# LPCB279_-_POWER.net
KiCad netlist of a schematic drawn in Altium Designer
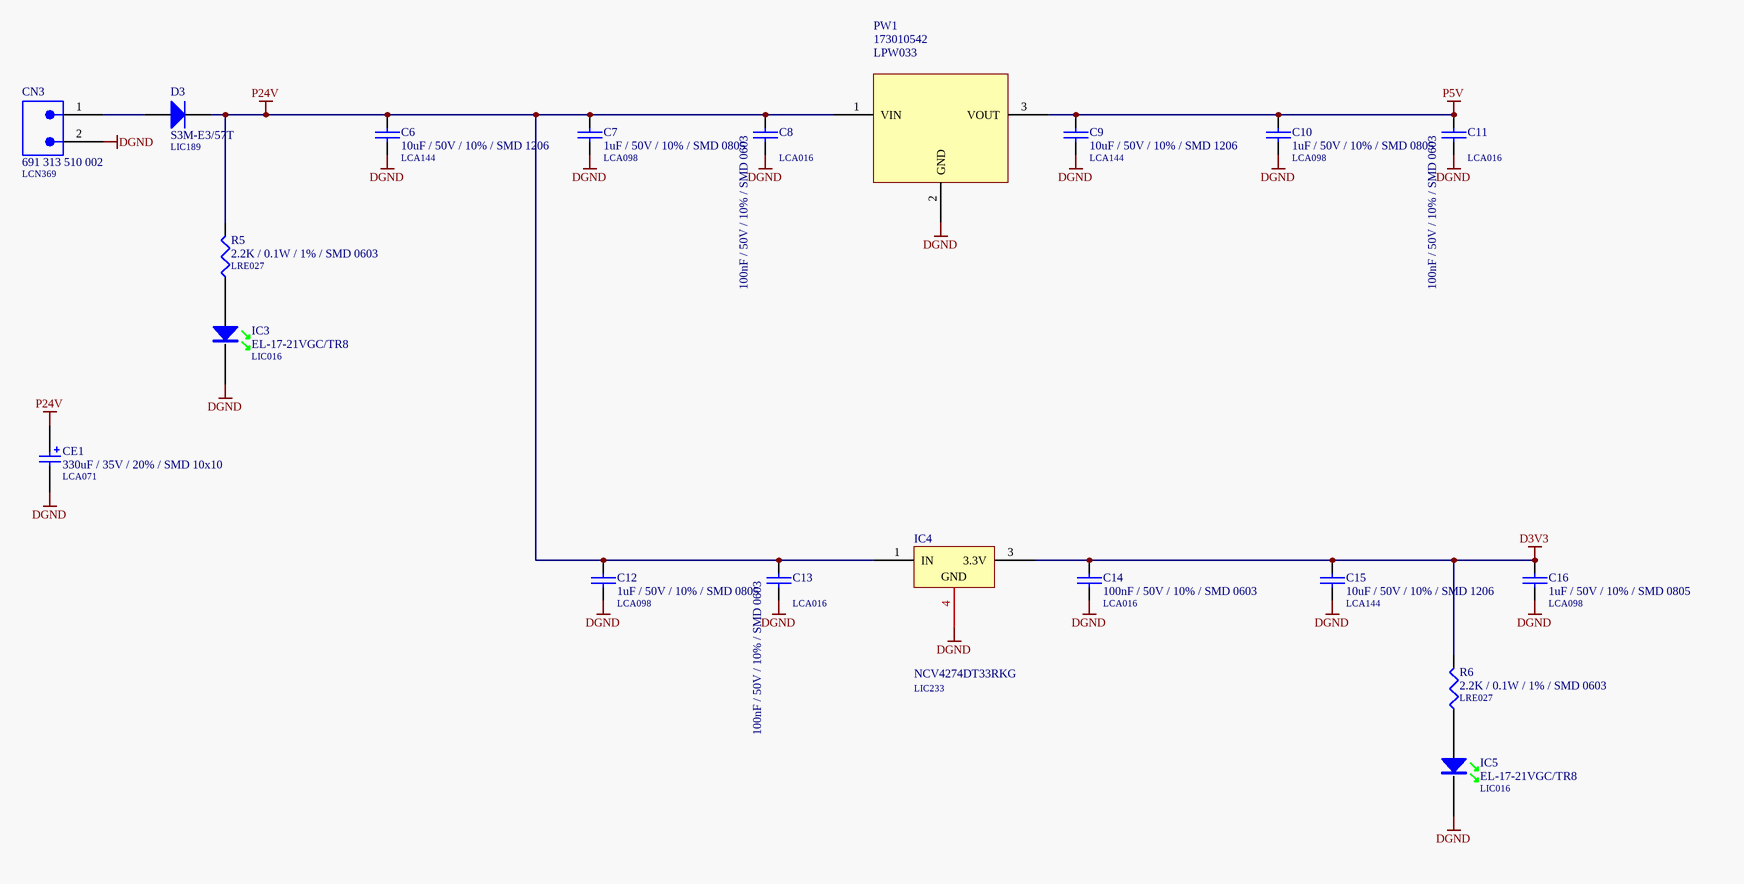
[diagram p0: LPCB279 - POWER.SchDoc]

(export (version "E")
  (design (tool "Eeschema 10.0.6"))
  (components
    (comp (ref "C6")
      (value "10uF / 50V / 10% / SMD 1206")
      (footprint "LFP043__CC3216-1206")
      (description "Capacitor, Ceramic Chip, 10uF, 50V, X5R, 10%, SMD 1206 [LCA144]")
      (fields (field (name "LDL_NUMBER") "LCA144"))
      (libsource (lib "LDL_Capacitors") (part "10uF / 50V / 10% / SMD 1206"))
    )
    (comp (ref "C7")
      (value "1uF / 50V / 10% / SMD 0805")
      (footprint "LFP010__CC2012-0805-IPC7351_B")
      (description "Capacitor, Ceramic Chip, 1uF, 50V, SMD 0805 [LCA098]")
      (fields (field (name "LDL_NUMBER") "LCA098"))
      (libsource (lib "LDL_Capacitors") (part "1uF / 50V / 10% / SMD 0805"))
    )
    (comp (ref "C8")
      (value "100nF / 50V / 10% / SMD 0603")
      (footprint "LFP011__CC1608-0603-IPC7351_B")
      (description "Capacitor, Ceramic Chip, 100nF (0.1uF), 50V, 5%, SMD 0603 [LCA016]")
      (fields (field (name "LDL_NUMBER") "LCA016"))
      (libsource (lib "LDL_Capacitors") (part "100nF / 50V / 10% / SMD 0603"))
    )
    (comp (ref "C9")
      (value "10uF / 50V / 10% / SMD 1206")
      (footprint "LFP043__CC3216-1206")
      (description "Capacitor, Ceramic Chip, 10uF, 50V, X5R, 10%, SMD 1206 [LCA144]")
      (fields (field (name "LDL_NUMBER") "LCA144"))
      (libsource (lib "LDL_Capacitors") (part "10uF / 50V / 10% / SMD 1206"))
    )
    (comp (ref "C10")
      (value "1uF / 50V / 10% / SMD 0805")
      (footprint "LFP010__CC2012-0805-IPC7351_B")
      (description "Capacitor, Ceramic Chip, 1uF, 50V, SMD 0805 [LCA098]")
      (fields (field (name "LDL_NUMBER") "LCA098"))
      (libsource (lib "LDL_Capacitors") (part "1uF / 50V / 10% / SMD 0805"))
    )
    (comp (ref "C11")
      (value "100nF / 50V / 10% / SMD 0603")
      (footprint "LFP011__CC1608-0603-IPC7351_B")
      (description "Capacitor, Ceramic Chip, 100nF (0.1uF), 50V, 5%, SMD 0603 [LCA016]")
      (fields (field (name "LDL_NUMBER") "LCA016"))
      (libsource (lib "LDL_Capacitors") (part "100nF / 50V / 10% / SMD 0603"))
    )
    (comp (ref "C12")
      (value "1uF / 50V / 10% / SMD 0805")
      (footprint "LFP010__CC2012-0805-IPC7351_B")
      (description "Capacitor, Ceramic Chip, 1uF, 50V, SMD 0805 [LCA098]")
      (fields (field (name "LDL_NUMBER") "LCA098"))
      (libsource (lib "LDL_Capacitors") (part "1uF / 50V / 10% / SMD 0805"))
    )
    (comp (ref "C13")
      (value "100nF / 50V / 10% / SMD 0603")
      (footprint "LFP011__CC1608-0603-IPC7351_B")
      (description "Capacitor, Ceramic Chip, 100nF (0.1uF), 50V, 5%, SMD 0603 [LCA016]")
      (fields (field (name "LDL_NUMBER") "LCA016"))
      (libsource (lib "LDL_Capacitors") (part "100nF / 50V / 10% / SMD 0603"))
    )
    (comp (ref "C14")
      (value "100nF / 50V / 10% / SMD 0603")
      (footprint "LFP011__CC1608-0603-IPC7351_B")
      (description "Capacitor, Ceramic Chip, 100nF (0.1uF), 50V, 5%, SMD 0603 [LCA016]")
      (fields (field (name "LDL_NUMBER") "LCA016"))
      (libsource (lib "LDL_Capacitors") (part "100nF / 50V / 10% / SMD 0603"))
    )
    (comp (ref "C15")
      (value "10uF / 50V / 10% / SMD 1206")
      (footprint "LFP043__CC3216-1206")
      (description "Capacitor, Ceramic Chip, 10uF, 50V, X5R, 10%, SMD 1206 [LCA144]")
      (fields (field (name "LDL_NUMBER") "LCA144"))
      (libsource (lib "LDL_Capacitors") (part "10uF / 50V / 10% / SMD 1206"))
    )
    (comp (ref "C16")
      (value "1uF / 50V / 10% / SMD 0805")
      (footprint "LFP010__CC2012-0805-IPC7351_B")
      (description "Capacitor, Ceramic Chip, 1uF, 50V, SMD 0805 [LCA098]")
      (fields (field (name "LDL_NUMBER") "LCA098"))
      (libsource (lib "LDL_Capacitors") (part "1uF / 50V / 10% / SMD 0805"))
    )
    (comp (ref "CE1")
      (value "330uF / 35V / 20% / SMD 10x10")
      (footprint "LFP041__NICHICON_WT_10X10")
      (description "Capacitor, Aluminum Electrolytic, 330uF, 35V, 20%, SMD (10mm x 10mm) [LCA071]")
      (fields (field (name "LDL_NUMBER") "LCA071"))
      (libsource (lib "LDL_Capacitors") (part "330uF / 35V / 20% / SMD 10x10"))
    )
    (comp (ref "CN3")
      (value "691 313 510 002")
      (footprint "691 313 510 002")
      (description "Connector, Pluggable Terminal Block, 5.08mm, 2 Way, PTH")
      (fields (field (name "LDL_NUMBER") "LCN369"))
      (libsource (lib "LDL_Connectors") (part "691 313 510 002"))
    )
    (comp (ref "D3")
      (value "S3M-E3/57T")
      (footprint "LFP040__DO-214AB")
      (description "Diode, General Purpose Rectifier, 3A, 200V, SMD DO-214AB [LIC189]")
      (fields (field (name "LDL_NUMBER") "LIC189"))
      (libsource (lib "LDL_Semiconductors") (part "S3M-E3/57T"))
    )
    (comp (ref "IC3")
      (value "EL-17-21VGC/TR8")
      (footprint "CR2012-0805-LED")
      (description "LED, SMD, 0805 Green [LIC016]")
      (fields (field (name "LDL_NUMBER") "LIC016"))
      (libsource (lib "LDL_Semiconductors") (part "EL-17-21VGC/TR8"))
    )
    (comp (ref "IC4")
      (value "NCV4274DT33RKG")
      (footprint "LFP019__369A-13")
      (description "IC, Voltage Regulator, 400mA, 3.3V LDO, SMD DPAK [LIC233]")
      (fields (field (name "LDL_NUMBER") "LIC233"))
      (libsource (lib "LDL_Semiconductors") (part "NCV4274DT33RKG"))
    )
    (comp (ref "IC5")
      (value "EL-17-21VGC/TR8")
      (footprint "CR2012-0805-LED")
      (description "LED, SMD, 0805 Green [LIC016]")
      (fields (field (name "LDL_NUMBER") "LIC016"))
      (libsource (lib "LDL_Semiconductors") (part "EL-17-21VGC/TR8"))
    )
    (comp (ref "PW1")
      (value "173010542")
      (footprint "173010542")
      (fields (field (name "LDL_NUMBER") "LPW033"))
      (libsource (lib "LDL_Power") (part "173010542"))
    )
    (comp (ref "R5")
      (value "2.2K / 0.1W / 1% / SMD 0603")
      (footprint "LFP020__CR1608-0603-IPC7351_B")
      (description "Resistor, Ceramic Chip, 2.2K, 0.1W, 1%, SMD 0603 [LRE027]")
      (fields (field (name "LDL_NUMBER") "LRE027"))
      (libsource (lib "LDL_Resistors") (part "2.2K / 0.1W / 1% / SMD 0603"))
    )
    (comp (ref "R6")
      (value "2.2K / 0.1W / 1% / SMD 0603")
      (footprint "LFP020__CR1608-0603-IPC7351_B")
      (description "Resistor, Ceramic Chip, 2.2K, 0.1W, 1%, SMD 0603 [LRE027]")
      (fields (field (name "LDL_NUMBER") "LRE027"))
      (libsource (lib "LDL_Resistors") (part "2.2K / 0.1W / 1% / SMD 0603"))
    )
  )
  (nets
    (net (code "1") (name "D3V3") (class "Default")
      (node (ref "C14") (pin "1") (pintype "passive"))
      (node (ref "C15") (pin "1") (pintype "passive"))
      (node (ref "C16") (pin "1") (pintype "passive"))
      (node (ref "IC4") (pin "3") (pinfunction "3.3V_3") (pintype "power_in"))
      (node (ref "R6") (pin "2") (pintype "passive"))
    )
    (net (code "2") (name "DGND") (class "Default")
      (node (ref "C10") (pin "2") (pintype "passive"))
      (node (ref "C11") (pin "2") (pintype "passive"))
      (node (ref "C12") (pin "2") (pintype "passive"))
      (node (ref "C13") (pin "2") (pintype "passive"))
      (node (ref "C14") (pin "2") (pintype "passive"))
      (node (ref "C15") (pin "2") (pintype "passive"))
      (node (ref "C16") (pin "2") (pintype "passive"))
      (node (ref "C6") (pin "2") (pintype "passive"))
      (node (ref "C7") (pin "2") (pintype "passive"))
      (node (ref "C8") (pin "2") (pintype "passive"))
      (node (ref "C9") (pin "2") (pintype "passive"))
      (node (ref "CE1") (pin "2") (pinfunction "2_2") (pintype "passive"))
      (node (ref "CN3") (pin "2") (pinfunction "2_2") (pintype "passive"))
      (node (ref "IC3") (pin "K") (pintype "passive"))
      (node (ref "IC4") (pin "4") (pinfunction "GND_4") (pintype "power_in"))
      (node (ref "IC5") (pin "K") (pintype "passive"))
      (node (ref "PW1") (pin "2") (pinfunction "GND_2") (pintype "passive"))
    )
    (net (code "3") (name "Net-(D3-A)") (class "Default")
      (node (ref "CN3") (pin "1") (pinfunction "1_1") (pintype "passive"))
      (node (ref "D3") (pin "2") (pinfunction "A_2") (pintype "passive"))
    )
    (net (code "4") (name "Net-(IC3-PadA)") (class "Default")
      (node (ref "IC3") (pin "A") (pintype "passive"))
      (node (ref "R5") (pin "1") (pintype "passive"))
    )
    (net (code "5") (name "Net-(IC5-PadA)") (class "Default")
      (node (ref "IC5") (pin "A") (pintype "passive"))
      (node (ref "R6") (pin "1") (pintype "passive"))
    )
    (net (code "6") (name "P5V") (class "Default")
      (node (ref "C10") (pin "1") (pintype "passive"))
      (node (ref "C11") (pin "1") (pintype "passive"))
      (node (ref "C9") (pin "1") (pintype "passive"))
      (node (ref "PW1") (pin "3") (pinfunction "VOUT_3") (pintype "passive"))
    )
    (net (code "7") (name "P24V") (class "Default")
      (node (ref "C12") (pin "1") (pintype "passive"))
      (node (ref "C13") (pin "1") (pintype "passive"))
      (node (ref "C6") (pin "1") (pintype "passive"))
      (node (ref "C7") (pin "1") (pintype "passive"))
      (node (ref "C8") (pin "1") (pintype "passive"))
      (node (ref "CE1") (pin "1") (pinfunction "1_1") (pintype "passive"))
      (node (ref "D3") (pin "1") (pinfunction "K_1") (pintype "passive"))
      (node (ref "IC4") (pin "1") (pinfunction "IN_1") (pintype "power_in"))
      (node (ref "PW1") (pin "1") (pinfunction "VIN_1") (pintype "passive"))
      (node (ref "R5") (pin "2") (pintype "passive"))
    )
  )
)
